# PMIC.net
KiCad netlist of a schematic drawn in Altium Designer
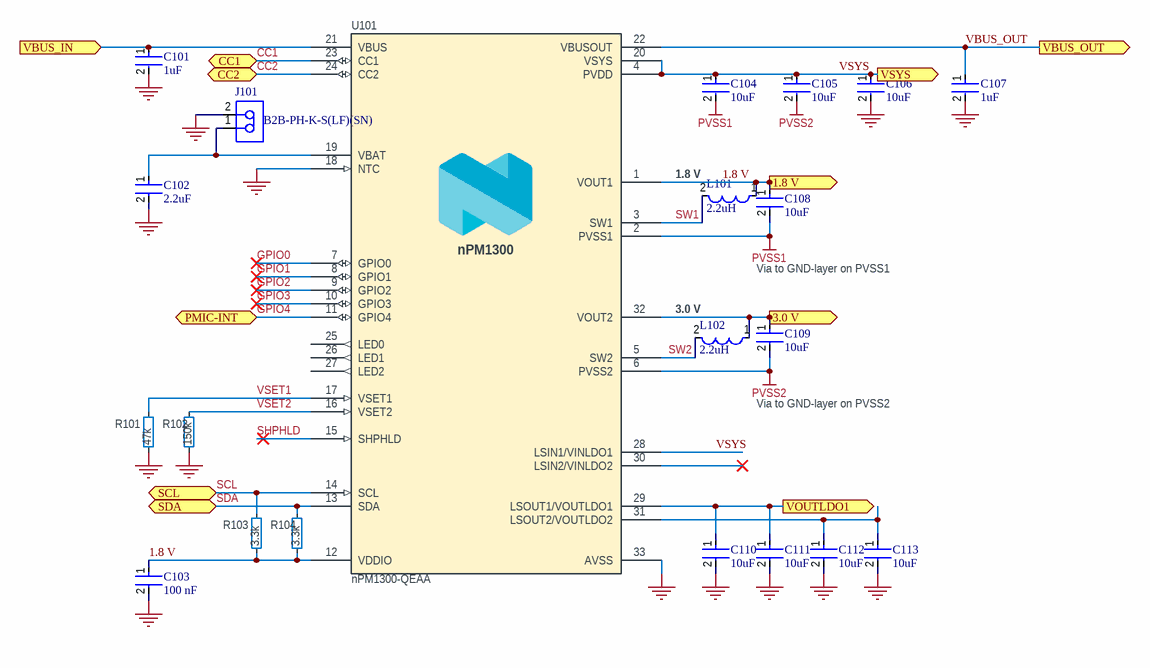
[diagram p0: PMIC (nPM1300).SchDoc]

(export (version "E")
  (design (tool "Eeschema 10.0.6"))
  (components
    (comp (ref "C101")
      (value "1uF")
      (footprint "FP-CL10-IPC_C")
      (description "Cap Ceramic 1uF 10V X5R ±10% Pad SMD 0603 +85°C T/R")
      (fields (field (name "TOLERANCE") "10%") (field (name "VOLTAGE") "10V"))
      (libsource (lib "Altium Content Vault") (part "b4654b650e69147ec39a6b967a45e02"))
    )
    (comp (ref "C102")
      (value "2.2uF")
      (footprint "FP-GRM188-0_2-MFG")
      (description "Chip Multilayer Ceramic Capacitors for General Purpose, 0603, 2.2uF, X7R, 15%, 10%, 16V")
      (libsource (lib "Altium Content Vault") (part "11868f565c42a9108669ba33697ecf6"))
    )
    (comp (ref "C103")
      (value "100 nF")
      (footprint "FP-CC0201-BA-MFG")
      (description "CAP CER 0.1UF 16V X5R 0201")
      (fields
        (field (name "MANUFACTURER PART NUMBER") "CC0201KRX5R7BB104")
        (field (name "MANUFACTURER") "Yageo")
      )
      (libsource (lib "Altium Content Vault") (part "11868f565c42a9108669ba33697ecf6"))
    )
    (comp (ref "C104")
      (value "10uF")
      (footprint "FP-GRM188-0_2-MFG")
      (description "Chip Multilayer Ceramic Capacitors for General Purpose, 0603, 10uF, X5R, 15%, 20%, 25V")
      (fields (field (name "TOLERANCE") "20%") (field (name "VOLTAGE") "25V"))
      (libsource (lib "Altium Content Vault") (part "11868f565c42a9108669ba33697ecf6"))
    )
    (comp (ref "C105")
      (value "10uF")
      (footprint "FP-GRM188-0_2-MFG")
      (description "Chip Multilayer Ceramic Capacitors for General Purpose, 0603, 10uF, X5R, 15%, 20%, 25V")
      (fields (field (name "TOLERANCE") "20%") (field (name "VOLTAGE") "25V"))
      (libsource (lib "Altium Content Vault") (part "11868f565c42a9108669ba33697ecf6"))
    )
    (comp (ref "C106")
      (value "10uF")
      (footprint "FP-GRM188-0_2-MFG")
      (description "Chip Multilayer Ceramic Capacitors for General Purpose, 0603, 10uF, X5R, 15%, 20%, 25V")
      (fields (field (name "TOLERANCE") "20%") (field (name "VOLTAGE") "25V"))
      (libsource (lib "Altium Content Vault") (part "11868f565c42a9108669ba33697ecf6"))
    )
    (comp (ref "C107")
      (value "1uF")
      (footprint "FP-CL10-IPC_C")
      (description "Cap Ceramic 1uF 10V X5R ±10% Pad SMD 0603 +85°C T/R")
      (fields (field (name "TOLERANCE") "10%") (field (name "VOLTAGE") "10V"))
      (libsource (lib "Altium Content Vault") (part "b4654b650e69147ec39a6b967a45e02"))
    )
    (comp (ref "C108")
      (value "10uF")
      (footprint "FP-GRM188-0_2-MFG")
      (description "Chip Multilayer Ceramic Capacitors for General Purpose, 0603, 10uF, X5R, 15%, 20%, 25V")
      (fields (field (name "TOLERANCE") "20%") (field (name "VOLTAGE") "25V"))
      (libsource (lib "Altium Content Vault") (part "11868f565c42a9108669ba33697ecf6"))
    )
    (comp (ref "C109")
      (value "10uF")
      (footprint "FP-GRM188-0_2-MFG")
      (description "Chip Multilayer Ceramic Capacitors for General Purpose, 0603, 10uF, X5R, 15%, 20%, 25V")
      (fields (field (name "TOLERANCE") "20%") (field (name "VOLTAGE") "25V"))
      (libsource (lib "Altium Content Vault") (part "11868f565c42a9108669ba33697ecf6"))
    )
    (comp (ref "C110")
      (value "10uF")
      (footprint "FP-GRM188-0_2-MFG")
      (description "Chip Multilayer Ceramic Capacitors for General Purpose, 0603, 10uF, X5R, 15%, 20%, 25V")
      (fields (field (name "TOLERANCE") "20%") (field (name "VOLTAGE") "25V"))
      (libsource (lib "Altium Content Vault") (part "11868f565c42a9108669ba33697ecf6"))
    )
    (comp (ref "C111")
      (value "10uF")
      (footprint "FP-GRM188-0_2-MFG")
      (description "Chip Multilayer Ceramic Capacitors for General Purpose, 0603, 10uF, X5R, 15%, 20%, 25V")
      (fields (field (name "TOLERANCE") "20%") (field (name "VOLTAGE") "25V"))
      (libsource (lib "Altium Content Vault") (part "11868f565c42a9108669ba33697ecf6"))
    )
    (comp (ref "C112")
      (value "10uF")
      (footprint "FP-GRM188-0_2-MFG")
      (description "Chip Multilayer Ceramic Capacitors for General Purpose, 0603, 10uF, X5R, 15%, 20%, 25V")
      (fields (field (name "TOLERANCE") "20%") (field (name "VOLTAGE") "25V"))
      (libsource (lib "Altium Content Vault") (part "11868f565c42a9108669ba33697ecf6"))
    )
    (comp (ref "C113")
      (value "10uF")
      (footprint "FP-GRM188-0_2-MFG")
      (description "Chip Multilayer Ceramic Capacitors for General Purpose, 0603, 10uF, X5R, 15%, 20%, 25V")
      (fields (field (name "TOLERANCE") "20%") (field (name "VOLTAGE") "25V"))
      (libsource (lib "Altium Content Vault") (part "11868f565c42a9108669ba33697ecf6"))
    )
    (comp (ref "J101")
      (value "B2B-PH-K-S(LF)(SN)")
      (footprint "JST-B2B-PH-K-S_V")
      (fields (field (name "MANUFACTURER") "JST"))
      (libsource (lib "Altium Content Vault") (part "CN-2P-F-QF2"))
    )
    (comp (ref "L101")
      (value "2.2uH")
      (footprint "FP-MLP2016M-IPC_B")
      (description "Shielded Multilayer Inductor 2.2uH ±20% 1200mA 143mΩ SMD 0806")
      (fields (field (name "TOLERANCE") "20%"))
      (libsource (lib "Altium Content Vault") (part "725321dda6339637d4d059423bc1c3c"))
    )
    (comp (ref "L102")
      (value "2.2uH")
      (footprint "FP-MLP2016M-IPC_B")
      (description "Shielded Multilayer Inductor 2.2uH ±20% 1200mA 143mΩ SMD 0806")
      (fields (field (name "TOLERANCE") "20%"))
      (libsource (lib "Altium Content Vault") (part "725321dda6339637d4d059423bc1c3c"))
    )
    (comp (ref "R101")
      (value "47k")
      (footprint "RESC0603X03L_C")
      (description "Resistor, ±1%, 0.05W")
      (fields (field (name "AUTHOR") "rsk"))
      (libsource (lib "Watch_Components") (part "R0201"))
    )
    (comp (ref "R102")
      (value "150k")
      (footprint "RESC0603X03L_C")
      (description "Resistor, ±1%, 0.05W")
      (fields (field (name "AUTHOR") "rsk"))
      (libsource (lib "Watch_Components") (part "R0201"))
    )
    (comp (ref "R103")
      (value "3.3k")
      (footprint "RESC0603X03L_C")
      (description "Resistor, ±1%, 0.05W")
      (fields (field (name "AUTHOR") "rsk"))
      (libsource (lib "Watch_Components") (part "R0201"))
    )
    (comp (ref "R104")
      (value "3.3k")
      (footprint "RESC0603X03L_C")
      (description "Resistor, ±1%, 0.05W")
      (fields (field (name "AUTHOR") "rsk"))
      (libsource (lib "Watch_Components") (part "R0201"))
    )
    (comp (ref "U101")
      (value "nPM1300-QEAA")
      (footprint "QFN32_5X5_NOR")
      (fields (field (name "MANUFACTURER") "Nordic Semiconductor") (field (name "AUTHOR") "eisk"))
      (libsource (lib "Watch_Components") (part "nPM1300_QEAA"))
    )
  )
  (nets
    (net (code "1") (name "/1.8 V") (class "Default")
      (node (ref "C103") (pin "1") (pinfunction "1_1") (pintype "passive"))
      (node (ref "C108") (pin "1") (pinfunction "1_1") (pintype "passive"))
      (node (ref "L101") (pin "1") (pinfunction "1_1") (pintype "passive"))
      (node (ref "R103") (pin "2") (pinfunction "2_2") (pintype "passive"))
      (node (ref "R104") (pin "2") (pinfunction "2_2") (pintype "passive"))
      (node (ref "U101") (pin "1") (pinfunction "VOUT1_1") (pintype "passive"))
      (node (ref "U101") (pin "12") (pinfunction "VDDIO_12") (pintype "power_in"))
    )
    (net (code "2") (name "/3.0 V") (class "Default")
      (node (ref "C109") (pin "1") (pinfunction "1_1") (pintype "passive"))
      (node (ref "L102") (pin "1") (pinfunction "1_1") (pintype "passive"))
      (node (ref "U101") (pin "32") (pinfunction "VOUT2_32") (pintype "passive"))
    )
    (net (code "3") (name "/CC1") (class "Default")
      (node (ref "U101") (pin "23") (pinfunction "CC1_23") (pintype "bidirectional"))
    )
    (net (code "4") (name "/CC2") (class "Default")
      (node (ref "U101") (pin "24") (pinfunction "CC2_24") (pintype "bidirectional"))
    )
    (net (code "5") (name "/GPIO0") (class "Default")
      (node (ref "U101") (pin "7") (pinfunction "GPIO0_7") (pintype "bidirectional+no_connect"))
    )
    (net (code "6") (name "/GPIO1") (class "Default")
      (node (ref "U101") (pin "8") (pinfunction "GPIO1_8") (pintype "bidirectional+no_connect"))
    )
    (net (code "7") (name "/GPIO2") (class "Default")
      (node (ref "U101") (pin "9") (pinfunction "GPIO2_9") (pintype "bidirectional+no_connect"))
    )
    (net (code "8") (name "/GPIO3") (class "Default")
      (node (ref "U101") (pin "10") (pinfunction "GPIO3_10") (pintype "bidirectional+no_connect"))
    )
    (net (code "9") (name "/GPIO4") (class "Default")
      (node (ref "U101") (pin "11") (pinfunction "GPIO4_11") (pintype "bidirectional"))
    )
    (net (code "10") (name "/SCL") (class "Default")
      (node (ref "R103") (pin "1") (pinfunction "1_1") (pintype "passive"))
      (node (ref "U101") (pin "14") (pinfunction "SCL_14") (pintype "input"))
    )
    (net (code "11") (name "/SDA") (class "Default")
      (node (ref "R104") (pin "1") (pinfunction "1_1") (pintype "passive"))
      (node (ref "U101") (pin "13") (pinfunction "SDA_13") (pintype "open_collector"))
    )
    (net (code "12") (name "/SHPHLD") (class "Default")
      (node (ref "U101") (pin "15") (pinfunction "SHPHLD_15") (pintype "input"))
    )
    (net (code "13") (name "/SW1") (class "Default")
      (node (ref "L101") (pin "2") (pinfunction "2_2") (pintype "passive"))
      (node (ref "U101") (pin "3") (pinfunction "SW1_3") (pintype "power_in"))
    )
    (net (code "14") (name "/SW2") (class "Default")
      (node (ref "L102") (pin "2") (pinfunction "2_2") (pintype "passive"))
      (node (ref "U101") (pin "5") (pinfunction "SW2_5") (pintype "power_in"))
    )
    (net (code "15") (name "/VBUS_IN") (class "Default")
      (node (ref "C101") (pin "1") (pinfunction "1_1") (pintype "passive"))
      (node (ref "U101") (pin "21") (pinfunction "VBUS_21") (pintype "passive"))
    )
    (net (code "16") (name "/VBUS_OUT") (class "Default")
      (node (ref "C107") (pin "1") (pinfunction "1_1") (pintype "passive"))
      (node (ref "U101") (pin "22") (pinfunction "VBUSOUT_22") (pintype "passive"))
    )
    (net (code "17") (name "/VOUTLDO1") (class "Default")
      (node (ref "C110") (pin "1") (pinfunction "1_1") (pintype "passive"))
      (node (ref "C111") (pin "1") (pinfunction "1_1") (pintype "passive"))
      (node (ref "U101") (pin "29") (pinfunction "LSOUT1/VOUTLDO1_29") (pintype "passive"))
    )
    (net (code "18") (name "/VSET1") (class "Default")
      (node (ref "R101") (pin "1") (pinfunction "1_1") (pintype "passive"))
      (node (ref "U101") (pin "17") (pinfunction "VSET1_17") (pintype "input"))
    )
    (net (code "19") (name "/VSET2") (class "Default")
      (node (ref "R102") (pin "1") (pinfunction "1_1") (pintype "passive"))
      (node (ref "U101") (pin "16") (pinfunction "VSET2_16") (pintype "input"))
    )
    (net (code "20") (name "/VSYS") (class "Default")
      (node (ref "C104") (pin "1") (pinfunction "1_1") (pintype "passive"))
      (node (ref "C105") (pin "1") (pinfunction "1_1") (pintype "passive"))
      (node (ref "C106") (pin "1") (pinfunction "1_1") (pintype "passive"))
      (node (ref "U101") (pin "20") (pinfunction "VSYS_20") (pintype "passive"))
      (node (ref "U101") (pin "28") (pinfunction "LSIN1/VINLDO1_28") (pintype "passive"))
      (node (ref "U101") (pin "4") (pinfunction "PVDD_4") (pintype "passive"))
    )
    (net (code "21") (name "GND") (class "Default")
      (node (ref "C101") (pin "2") (pinfunction "2_2") (pintype "passive"))
      (node (ref "C102") (pin "2") (pinfunction "2_2") (pintype "passive"))
      (node (ref "C103") (pin "2") (pinfunction "2_2") (pintype "passive"))
      (node (ref "C106") (pin "2") (pinfunction "2_2") (pintype "passive"))
      (node (ref "C107") (pin "2") (pinfunction "2_2") (pintype "passive"))
      (node (ref "C110") (pin "2") (pinfunction "2_2") (pintype "passive"))
      (node (ref "C111") (pin "2") (pinfunction "2_2") (pintype "passive"))
      (node (ref "C112") (pin "2") (pinfunction "2_2") (pintype "passive"))
      (node (ref "C113") (pin "2") (pinfunction "2_2") (pintype "passive"))
      (node (ref "J101") (pin "2") (pinfunction "2_2") (pintype "passive"))
      (node (ref "R101") (pin "2") (pinfunction "2_2") (pintype "passive"))
      (node (ref "R102") (pin "2") (pinfunction "2_2") (pintype "passive"))
      (node (ref "U101") (pin "18") (pinfunction "NTC_18") (pintype "input"))
      (node (ref "U101") (pin "33") (pinfunction "AVSS_33") (pintype "power_in"))
    )
    (net (code "22") (name "Net-(U101-LSOUT2{slash}VOUTLDO2)") (class "Default")
      (node (ref "C112") (pin "1") (pinfunction "1_1") (pintype "passive"))
      (node (ref "C113") (pin "1") (pinfunction "1_1") (pintype "passive"))
      (node (ref "U101") (pin "31") (pinfunction "LSOUT2/VOUTLDO2_31") (pintype "passive"))
    )
    (net (code "23") (name "Net-(U101-VBAT)") (class "Default")
      (node (ref "C102") (pin "1") (pinfunction "1_1") (pintype "passive"))
      (node (ref "J101") (pin "1") (pinfunction "1_1") (pintype "passive"))
      (node (ref "U101") (pin "19") (pinfunction "VBAT_19") (pintype "passive"))
    )
    (net (code "24") (name "PVSS1") (class "Default")
      (node (ref "C104") (pin "2") (pinfunction "2_2") (pintype "passive"))
      (node (ref "C108") (pin "2") (pinfunction "2_2") (pintype "passive"))
      (node (ref "U101") (pin "2") (pinfunction "PVSS1_2") (pintype "power_in"))
    )
    (net (code "25") (name "PVSS2") (class "Default")
      (node (ref "C105") (pin "2") (pinfunction "2_2") (pintype "passive"))
      (node (ref "C109") (pin "2") (pinfunction "2_2") (pintype "passive"))
      (node (ref "U101") (pin "6") (pinfunction "PVSS2_6") (pintype "power_in"))
    )
    (net (code "26") (name "unconnected-(U101-LED0-Pad25)") (class "Default")
      (node (ref "U101") (pin "25") (pinfunction "LED0_25") (pintype "output"))
    )
    (net (code "27") (name "unconnected-(U101-LED1-Pad26)") (class "Default")
      (node (ref "U101") (pin "26") (pinfunction "LED1_26") (pintype "output"))
    )
    (net (code "28") (name "unconnected-(U101-LED2-Pad27)") (class "Default")
      (node (ref "U101") (pin "27") (pinfunction "LED2_27") (pintype "output"))
    )
    (net (code "29") (name "unconnected-(U101-LSIN2{slash}VINLDO2-Pad30)") (class "Default")
      (node (ref "U101") (pin "30") (pinfunction "LSIN2/VINLDO2_30") (pintype "passive+no_connect"))
    )
  )
)
